# scorpion_shield_mega.net
KiCad netlist of a schematic drawn in EAGLE
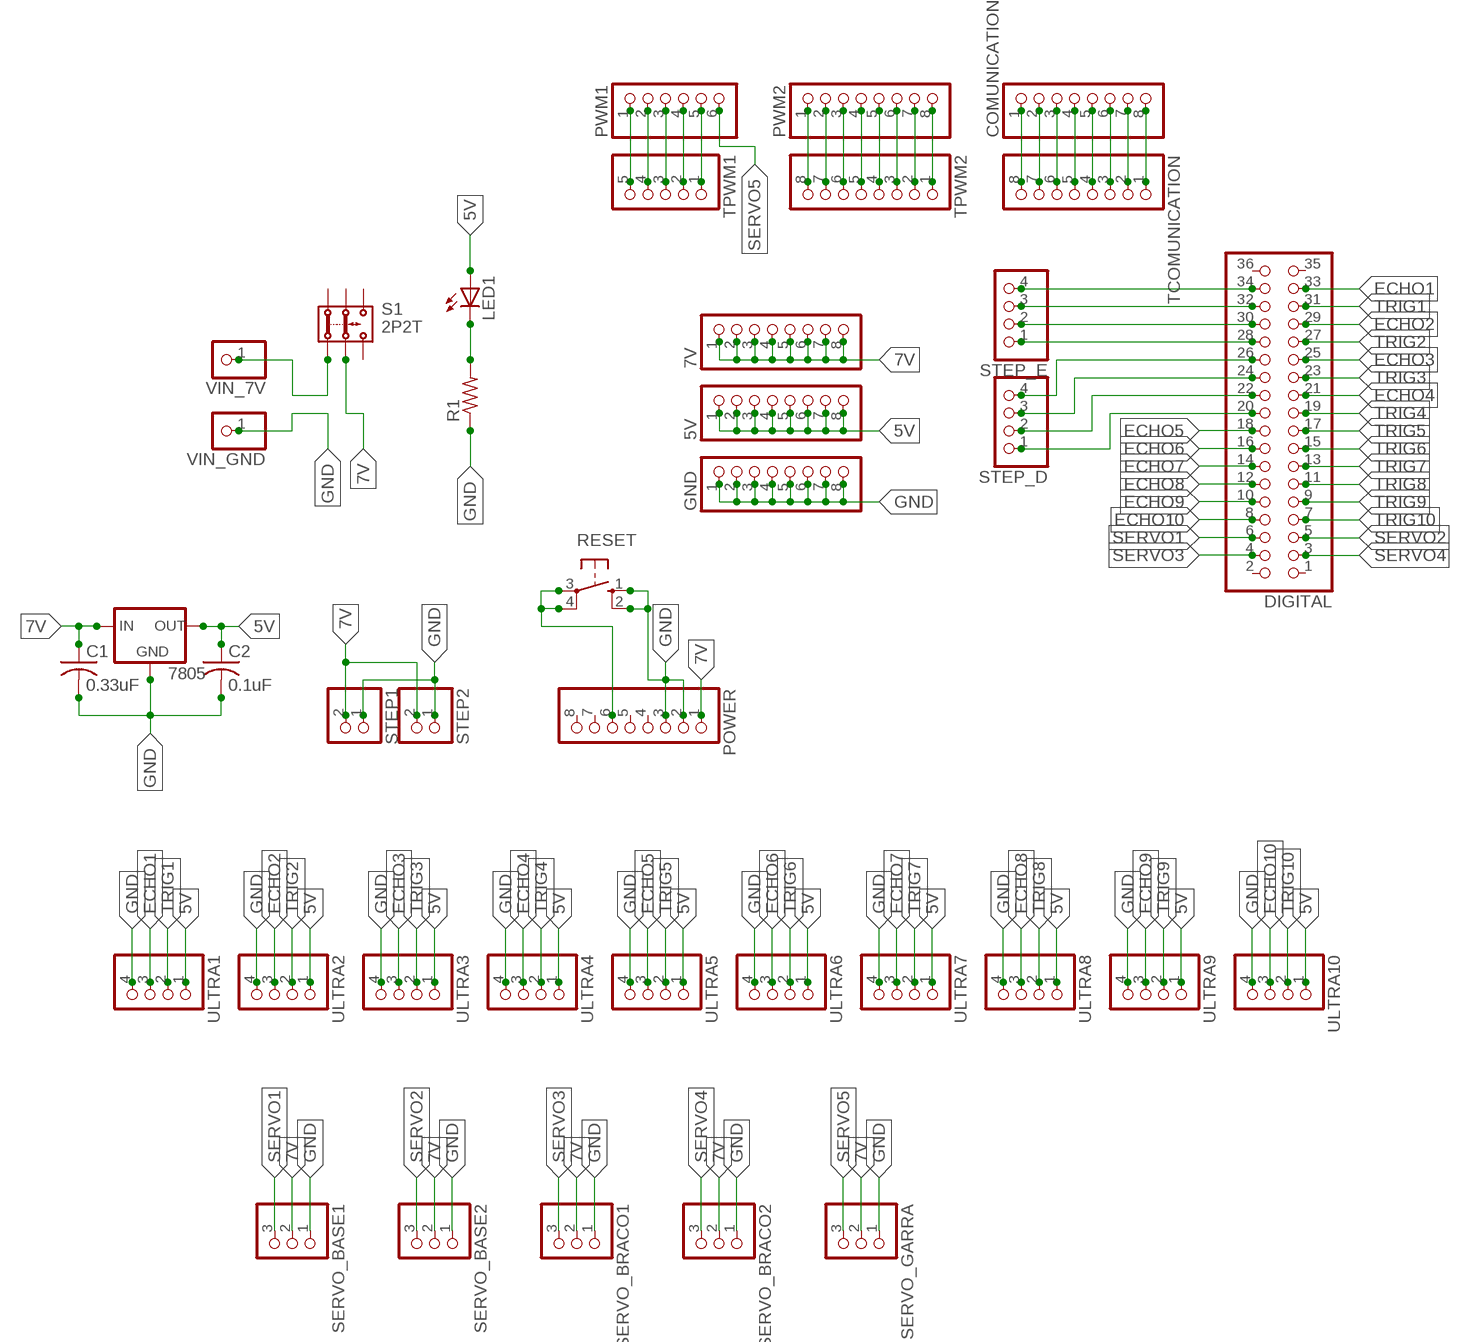
[diagram p0: schematic, sheet 1]

(export (version "E")
  (design (tool "Eeschema 10.0.6"))
  (components
    (comp (ref "5V")
      (value "PINHD-1X8")
      (footprint "eagle-import:1X08")
      (libsource (lib "eagle-import") (part "PINHD-1X8"))
    )
    (comp (ref "7V")
      (value "PINHD-1X8")
      (footprint "eagle-import:1X08")
      (libsource (lib "eagle-import") (part "PINHD-1X8"))
    )
    (comp (ref "7805")
      (value "78XXS")
      (footprint "eagle-import:78XXS")
      (libsource (lib "eagle-import") (part "78XXS"))
    )
    (comp (ref "C1")
      (value "0.33uF")
      (footprint "eagle-import:C050-025X075")
      (libsource (lib "eagle-import") (part "C-US050-025X075"))
    )
    (comp (ref "C2")
      (value "0.1uF")
      (footprint "eagle-import:C050-025X075")
      (libsource (lib "eagle-import") (part "C-US050-025X075"))
    )
    (comp (ref "COMUNICATION")
      (value "PINHD-1X8")
      (footprint "eagle-import:1X08")
      (libsource (lib "eagle-import") (part "PINHD-1X8"))
    )
    (comp (ref "DIGITAL")
      (value "PINHD-2X18")
      (footprint "eagle-import:2X18")
      (libsource (lib "eagle-import") (part "PINHD-2X18"))
    )
    (comp (ref "GND")
      (value "PINHD-1X8")
      (footprint "eagle-import:1X08")
      (libsource (lib "eagle-import") (part "PINHD-1X8"))
    )
    (comp (ref "LED1")
      (value "LED5MM")
      (footprint "eagle-import:LED5MM")
      (libsource (lib "eagle-import") (part "LED5MM"))
    )
    (comp (ref "POWER")
      (value "PINHD-1X8")
      (footprint "eagle-import:1X08")
      (libsource (lib "eagle-import") (part "PINHD-1X8"))
    )
    (comp (ref "PWM1")
      (value "PINHD-1X6")
      (footprint "eagle-import:1X06")
      (libsource (lib "eagle-import") (part "PINHD-1X6"))
    )
    (comp (ref "PWM2")
      (value "PINHD-1X8")
      (footprint "eagle-import:1X08")
      (libsource (lib "eagle-import") (part "PINHD-1X8"))
    )
    (comp (ref "R1")
      (value "R-US_0204/7")
      (footprint "eagle-import:0204_7")
      (libsource (lib "eagle-import") (part "R-US_0204/7"))
    )
    (comp (ref "RESET")
      (value "10-XX")
      (footprint "eagle-import:B3F-10XX")
      (fields (field (name "MPN") "B3F-1000"))
      (libsource (lib "eagle-import") (part "10-XX"))
    )
    (comp (ref "S1")
      (value "2P2T")
      (footprint "eagle-import:2P2T")
      (libsource (lib "eagle-import") (part "2P2T"))
    )
    (comp (ref "SERVO_BASE1")
      (value "PINHD-1X3")
      (footprint "eagle-import:1X03")
      (libsource (lib "eagle-import") (part "PINHD-1X3"))
    )
    (comp (ref "SERVO_BASE2")
      (value "PINHD-1X3")
      (footprint "eagle-import:1X03")
      (libsource (lib "eagle-import") (part "PINHD-1X3"))
    )
    (comp (ref "SERVO_BRACO1")
      (value "PINHD-1X3")
      (footprint "eagle-import:1X03")
      (libsource (lib "eagle-import") (part "PINHD-1X3"))
    )
    (comp (ref "SERVO_BRACO2")
      (value "PINHD-1X3")
      (footprint "eagle-import:1X03")
      (libsource (lib "eagle-import") (part "PINHD-1X3"))
    )
    (comp (ref "SERVO_GARRA")
      (value "PINHD-1X3")
      (footprint "eagle-import:1X03")
      (libsource (lib "eagle-import") (part "PINHD-1X3"))
    )
    (comp (ref "STEP1")
      (value "PINHD-1X2")
      (footprint "eagle-import:1X02")
      (libsource (lib "eagle-import") (part "PINHD-1X2"))
    )
    (comp (ref "STEP2")
      (value "PINHD-1X2")
      (footprint "eagle-import:1X02")
      (libsource (lib "eagle-import") (part "PINHD-1X2"))
    )
    (comp (ref "STEP_D")
      (value "PINHD-1X4")
      (footprint "eagle-import:1X04")
      (libsource (lib "eagle-import") (part "PINHD-1X4"))
    )
    (comp (ref "STEP_E")
      (value "PINHD-1X4")
      (footprint "eagle-import:1X04")
      (libsource (lib "eagle-import") (part "PINHD-1X4"))
    )
    (comp (ref "TCOMUNICATION")
      (value "PINHD-1X8")
      (footprint "eagle-import:1X08")
      (libsource (lib "eagle-import") (part "PINHD-1X8"))
    )
    (comp (ref "TPWM1")
      (value "PINHD-1X5")
      (footprint "eagle-import:1X05")
      (libsource (lib "eagle-import") (part "PINHD-1X5"))
    )
    (comp (ref "TPWM2")
      (value "PINHD-1X8")
      (footprint "eagle-import:1X08")
      (libsource (lib "eagle-import") (part "PINHD-1X8"))
    )
    (comp (ref "ULTRA1")
      (value "PINHD-1X4")
      (footprint "eagle-import:1X04")
      (libsource (lib "eagle-import") (part "PINHD-1X4"))
    )
    (comp (ref "ULTRA2")
      (value "PINHD-1X4")
      (footprint "eagle-import:1X04")
      (libsource (lib "eagle-import") (part "PINHD-1X4"))
    )
    (comp (ref "ULTRA3")
      (value "PINHD-1X4")
      (footprint "eagle-import:1X04")
      (libsource (lib "eagle-import") (part "PINHD-1X4"))
    )
    (comp (ref "ULTRA4")
      (value "PINHD-1X4")
      (footprint "eagle-import:1X04")
      (libsource (lib "eagle-import") (part "PINHD-1X4"))
    )
    (comp (ref "ULTRA5")
      (value "PINHD-1X4")
      (footprint "eagle-import:1X04")
      (libsource (lib "eagle-import") (part "PINHD-1X4"))
    )
    (comp (ref "ULTRA6")
      (value "PINHD-1X4")
      (footprint "eagle-import:1X04")
      (libsource (lib "eagle-import") (part "PINHD-1X4"))
    )
    (comp (ref "ULTRA7")
      (value "PINHD-1X4")
      (footprint "eagle-import:1X04")
      (libsource (lib "eagle-import") (part "PINHD-1X4"))
    )
    (comp (ref "ULTRA8")
      (value "PINHD-1X4")
      (footprint "eagle-import:1X04")
      (libsource (lib "eagle-import") (part "PINHD-1X4"))
    )
    (comp (ref "ULTRA9")
      (value "PINHD-1X4")
      (footprint "eagle-import:1X04")
      (libsource (lib "eagle-import") (part "PINHD-1X4"))
    )
    (comp (ref "ULTRA10")
      (value "PINHD-1X4")
      (footprint "eagle-import:1X04")
      (libsource (lib "eagle-import") (part "PINHD-1X4"))
    )
    (comp (ref "VIN_7V")
      (value "PINHD-1X1")
      (footprint "eagle-import:1X01")
      (libsource (lib "eagle-import") (part "PINHD-1X1"))
    )
    (comp (ref "VIN_GND")
      (value "PINHD-1X1")
      (footprint "eagle-import:1X01")
      (libsource (lib "eagle-import") (part "PINHD-1X1"))
    )
  )
  (nets
    (net (code "1") (name "5V") (class "Default")
      (node (ref "5V") (pin "1") (pinfunction "1_1") (pintype "passive"))
      (node (ref "5V") (pin "2") (pinfunction "2_2") (pintype "passive"))
      (node (ref "5V") (pin "3") (pinfunction "3_3") (pintype "passive"))
      (node (ref "5V") (pin "4") (pinfunction "4_4") (pintype "passive"))
      (node (ref "5V") (pin "5") (pinfunction "5_5") (pintype "passive"))
      (node (ref "5V") (pin "6") (pinfunction "6_6") (pintype "passive"))
      (node (ref "5V") (pin "7") (pinfunction "7_7") (pintype "passive"))
      (node (ref "5V") (pin "8") (pinfunction "8_8") (pintype "passive"))
      (node (ref "7805") (pin "OUT") (pinfunction "OUT_OUT") (pintype "passive"))
      (node (ref "C2") (pin "1") (pinfunction "1_1") (pintype "passive"))
      (node (ref "LED1") (pin "A") (pinfunction "A_A") (pintype "passive"))
      (node (ref "ULTRA1") (pin "1") (pinfunction "1_1") (pintype "passive"))
      (node (ref "ULTRA10") (pin "1") (pinfunction "1_1") (pintype "passive"))
      (node (ref "ULTRA2") (pin "1") (pinfunction "1_1") (pintype "passive"))
      (node (ref "ULTRA3") (pin "1") (pinfunction "1_1") (pintype "passive"))
      (node (ref "ULTRA4") (pin "1") (pinfunction "1_1") (pintype "passive"))
      (node (ref "ULTRA5") (pin "1") (pinfunction "1_1") (pintype "passive"))
      (node (ref "ULTRA6") (pin "1") (pinfunction "1_1") (pintype "passive"))
      (node (ref "ULTRA7") (pin "1") (pinfunction "1_1") (pintype "passive"))
      (node (ref "ULTRA8") (pin "1") (pinfunction "1_1") (pintype "passive"))
      (node (ref "ULTRA9") (pin "1") (pinfunction "1_1") (pintype "passive"))
    )
    (net (code "2") (name "7V") (class "Default")
      (node (ref "7805") (pin "IN") (pinfunction "IN_IN") (pintype "input"))
      (node (ref "7V") (pin "1") (pinfunction "1_1") (pintype "passive"))
      (node (ref "7V") (pin "2") (pinfunction "2_2") (pintype "passive"))
      (node (ref "7V") (pin "3") (pinfunction "3_3") (pintype "passive"))
      (node (ref "7V") (pin "4") (pinfunction "4_4") (pintype "passive"))
      (node (ref "7V") (pin "5") (pinfunction "5_5") (pintype "passive"))
      (node (ref "7V") (pin "6") (pinfunction "6_6") (pintype "passive"))
      (node (ref "7V") (pin "7") (pinfunction "7_7") (pintype "passive"))
      (node (ref "7V") (pin "8") (pinfunction "8_8") (pintype "passive"))
      (node (ref "C1") (pin "1") (pinfunction "1_1") (pintype "passive"))
      (node (ref "POWER") (pin "1") (pinfunction "1_1") (pintype "passive"))
      (node (ref "S1") (pin "2.2") (pinfunction "2.2_2.2") (pintype "passive"))
      (node (ref "SERVO_BASE1") (pin "2") (pinfunction "2_2") (pintype "passive"))
      (node (ref "SERVO_BASE2") (pin "2") (pinfunction "2_2") (pintype "passive"))
      (node (ref "SERVO_BRACO1") (pin "2") (pinfunction "2_2") (pintype "passive"))
      (node (ref "SERVO_BRACO2") (pin "2") (pinfunction "2_2") (pintype "passive"))
      (node (ref "SERVO_GARRA") (pin "2") (pinfunction "2_2") (pintype "passive"))
      (node (ref "STEP1") (pin "2") (pinfunction "2_2") (pintype "passive"))
      (node (ref "STEP2") (pin "2") (pinfunction "2_2") (pintype "passive"))
    )
    (net (code "3") (name "ECHO1") (class "Default")
      (node (ref "DIGITAL") (pin "33") (pinfunction "33_33") (pintype "passive"))
      (node (ref "ULTRA1") (pin "3") (pinfunction "3_3") (pintype "passive"))
    )
    (net (code "4") (name "ECHO2") (class "Default")
      (node (ref "DIGITAL") (pin "29") (pinfunction "29_29") (pintype "passive"))
      (node (ref "ULTRA2") (pin "3") (pinfunction "3_3") (pintype "passive"))
    )
    (net (code "5") (name "ECHO3") (class "Default")
      (node (ref "DIGITAL") (pin "25") (pinfunction "25_25") (pintype "passive"))
      (node (ref "ULTRA3") (pin "3") (pinfunction "3_3") (pintype "passive"))
    )
    (net (code "6") (name "ECHO4") (class "Default")
      (node (ref "DIGITAL") (pin "21") (pinfunction "21_21") (pintype "passive"))
      (node (ref "ULTRA4") (pin "3") (pinfunction "3_3") (pintype "passive"))
    )
    (net (code "7") (name "ECHO5") (class "Default")
      (node (ref "DIGITAL") (pin "18") (pinfunction "18_18") (pintype "passive"))
      (node (ref "ULTRA5") (pin "3") (pinfunction "3_3") (pintype "passive"))
    )
    (net (code "8") (name "ECHO6") (class "Default")
      (node (ref "DIGITAL") (pin "16") (pinfunction "16_16") (pintype "passive"))
      (node (ref "ULTRA6") (pin "3") (pinfunction "3_3") (pintype "passive"))
    )
    (net (code "9") (name "ECHO7") (class "Default")
      (node (ref "DIGITAL") (pin "14") (pinfunction "14_14") (pintype "passive"))
      (node (ref "ULTRA7") (pin "3") (pinfunction "3_3") (pintype "passive"))
    )
    (net (code "10") (name "ECHO8") (class "Default")
      (node (ref "DIGITAL") (pin "12") (pinfunction "12_12") (pintype "passive"))
      (node (ref "ULTRA8") (pin "3") (pinfunction "3_3") (pintype "passive"))
    )
    (net (code "11") (name "ECHO9") (class "Default")
      (node (ref "DIGITAL") (pin "10") (pinfunction "10_10") (pintype "passive"))
      (node (ref "ULTRA9") (pin "3") (pinfunction "3_3") (pintype "passive"))
    )
    (net (code "12") (name "ECHO10") (class "Default")
      (node (ref "DIGITAL") (pin "8") (pinfunction "8_8") (pintype "passive"))
      (node (ref "ULTRA10") (pin "3") (pinfunction "3_3") (pintype "passive"))
    )
    (net (code "13") (name "GND") (class "Default")
      (node (ref "7805") (pin "GND") (pinfunction "GND_GND") (pintype "input"))
      (node (ref "C1") (pin "2") (pinfunction "2_2") (pintype "passive"))
      (node (ref "C2") (pin "2") (pinfunction "2_2") (pintype "passive"))
      (node (ref "GND") (pin "1") (pinfunction "1_1") (pintype "passive"))
      (node (ref "GND") (pin "2") (pinfunction "2_2") (pintype "passive"))
      (node (ref "GND") (pin "3") (pinfunction "3_3") (pintype "passive"))
      (node (ref "GND") (pin "4") (pinfunction "4_4") (pintype "passive"))
      (node (ref "GND") (pin "5") (pinfunction "5_5") (pintype "passive"))
      (node (ref "GND") (pin "6") (pinfunction "6_6") (pintype "passive"))
      (node (ref "GND") (pin "7") (pinfunction "7_7") (pintype "passive"))
      (node (ref "GND") (pin "8") (pinfunction "8_8") (pintype "passive"))
      (node (ref "POWER") (pin "2") (pinfunction "2_2") (pintype "passive"))
      (node (ref "POWER") (pin "3") (pinfunction "3_3") (pintype "passive"))
      (node (ref "R1") (pin "1") (pinfunction "1_1") (pintype "passive"))
      (node (ref "RESET") (pin "1") (pinfunction "S_1") (pintype "passive"))
      (node (ref "RESET") (pin "2") (pinfunction "S1_2") (pintype "passive"))
      (node (ref "SERVO_BASE1") (pin "1") (pinfunction "1_1") (pintype "passive"))
      (node (ref "SERVO_BASE2") (pin "1") (pinfunction "1_1") (pintype "passive"))
      (node (ref "SERVO_BRACO1") (pin "1") (pinfunction "1_1") (pintype "passive"))
      (node (ref "SERVO_BRACO2") (pin "1") (pinfunction "1_1") (pintype "passive"))
      (node (ref "SERVO_GARRA") (pin "1") (pinfunction "1_1") (pintype "passive"))
      (node (ref "STEP1") (pin "1") (pinfunction "1_1") (pintype "passive"))
      (node (ref "STEP2") (pin "1") (pinfunction "1_1") (pintype "passive"))
      (node (ref "ULTRA1") (pin "4") (pinfunction "4_4") (pintype "passive"))
      (node (ref "ULTRA10") (pin "4") (pinfunction "4_4") (pintype "passive"))
      (node (ref "ULTRA2") (pin "4") (pinfunction "4_4") (pintype "passive"))
      (node (ref "ULTRA3") (pin "4") (pinfunction "4_4") (pintype "passive"))
      (node (ref "ULTRA4") (pin "4") (pinfunction "4_4") (pintype "passive"))
      (node (ref "ULTRA5") (pin "4") (pinfunction "4_4") (pintype "passive"))
      (node (ref "ULTRA6") (pin "4") (pinfunction "4_4") (pintype "passive"))
      (node (ref "ULTRA7") (pin "4") (pinfunction "4_4") (pintype "passive"))
      (node (ref "ULTRA8") (pin "4") (pinfunction "4_4") (pintype "passive"))
      (node (ref "ULTRA9") (pin "4") (pinfunction "4_4") (pintype "passive"))
      (node (ref "VIN_GND") (pin "1") (pinfunction "1_1") (pintype "passive"))
    )
    (net (code "14") (name "Net-(COMUNICATION-Pad1)") (class "Default")
      (node (ref "COMUNICATION") (pin "1") (pinfunction "1_1") (pintype "passive"))
      (node (ref "TCOMUNICATION") (pin "8") (pinfunction "8_8") (pintype "passive"))
    )
    (net (code "15") (name "Net-(COMUNICATION-Pad2)") (class "Default")
      (node (ref "COMUNICATION") (pin "2") (pinfunction "2_2") (pintype "passive"))
      (node (ref "TCOMUNICATION") (pin "7") (pinfunction "7_7") (pintype "passive"))
    )
    (net (code "16") (name "Net-(COMUNICATION-Pad3)") (class "Default")
      (node (ref "COMUNICATION") (pin "3") (pinfunction "3_3") (pintype "passive"))
      (node (ref "TCOMUNICATION") (pin "6") (pinfunction "6_6") (pintype "passive"))
    )
    (net (code "17") (name "Net-(COMUNICATION-Pad4)") (class "Default")
      (node (ref "COMUNICATION") (pin "4") (pinfunction "4_4") (pintype "passive"))
      (node (ref "TCOMUNICATION") (pin "5") (pinfunction "5_5") (pintype "passive"))
    )
    (net (code "18") (name "Net-(COMUNICATION-Pad5)") (class "Default")
      (node (ref "COMUNICATION") (pin "5") (pinfunction "5_5") (pintype "passive"))
      (node (ref "TCOMUNICATION") (pin "4") (pinfunction "4_4") (pintype "passive"))
    )
    (net (code "19") (name "Net-(COMUNICATION-Pad6)") (class "Default")
      (node (ref "COMUNICATION") (pin "6") (pinfunction "6_6") (pintype "passive"))
      (node (ref "TCOMUNICATION") (pin "3") (pinfunction "3_3") (pintype "passive"))
    )
    (net (code "20") (name "Net-(COMUNICATION-Pad7)") (class "Default")
      (node (ref "COMUNICATION") (pin "7") (pinfunction "7_7") (pintype "passive"))
      (node (ref "TCOMUNICATION") (pin "2") (pinfunction "2_2") (pintype "passive"))
    )
    (net (code "21") (name "Net-(COMUNICATION-Pad8)") (class "Default")
      (node (ref "COMUNICATION") (pin "8") (pinfunction "8_8") (pintype "passive"))
      (node (ref "TCOMUNICATION") (pin "1") (pinfunction "1_1") (pintype "passive"))
    )
    (net (code "22") (name "Net-(DIGITAL-Pad20)") (class "Default")
      (node (ref "DIGITAL") (pin "20") (pinfunction "20_20") (pintype "passive"))
      (node (ref "STEP_D") (pin "1") (pinfunction "1_1") (pintype "passive"))
    )
    (net (code "23") (name "Net-(DIGITAL-Pad22)") (class "Default")
      (node (ref "DIGITAL") (pin "22") (pinfunction "22_22") (pintype "passive"))
      (node (ref "STEP_D") (pin "2") (pinfunction "2_2") (pintype "passive"))
    )
    (net (code "24") (name "Net-(DIGITAL-Pad24)") (class "Default")
      (node (ref "DIGITAL") (pin "24") (pinfunction "24_24") (pintype "passive"))
      (node (ref "STEP_D") (pin "3") (pinfunction "3_3") (pintype "passive"))
    )
    (net (code "25") (name "Net-(DIGITAL-Pad26)") (class "Default")
      (node (ref "DIGITAL") (pin "26") (pinfunction "26_26") (pintype "passive"))
      (node (ref "STEP_D") (pin "4") (pinfunction "4_4") (pintype "passive"))
    )
    (net (code "26") (name "Net-(DIGITAL-Pad28)") (class "Default")
      (node (ref "DIGITAL") (pin "28") (pinfunction "28_28") (pintype "passive"))
      (node (ref "STEP_E") (pin "1") (pinfunction "1_1") (pintype "passive"))
    )
    (net (code "27") (name "Net-(DIGITAL-Pad30)") (class "Default")
      (node (ref "DIGITAL") (pin "30") (pinfunction "30_30") (pintype "passive"))
      (node (ref "STEP_E") (pin "2") (pinfunction "2_2") (pintype "passive"))
    )
    (net (code "28") (name "Net-(DIGITAL-Pad32)") (class "Default")
      (node (ref "DIGITAL") (pin "32") (pinfunction "32_32") (pintype "passive"))
      (node (ref "STEP_E") (pin "3") (pinfunction "3_3") (pintype "passive"))
    )
    (net (code "29") (name "Net-(DIGITAL-Pad34)") (class "Default")
      (node (ref "DIGITAL") (pin "34") (pinfunction "34_34") (pintype "passive"))
      (node (ref "STEP_E") (pin "4") (pinfunction "4_4") (pintype "passive"))
    )
    (net (code "30") (name "Net-(LED1-C)") (class "Default")
      (node (ref "LED1") (pin "K") (pinfunction "C_K") (pintype "passive"))
      (node (ref "R1") (pin "2") (pinfunction "2_2") (pintype "passive"))
    )
    (net (code "31") (name "Net-(PWM1-Pad1)") (class "Default")
      (node (ref "PWM1") (pin "1") (pinfunction "1_1") (pintype "passive"))
      (node (ref "TPWM1") (pin "5") (pinfunction "5_5") (pintype "passive"))
    )
    (net (code "32") (name "Net-(PWM1-Pad2)") (class "Default")
      (node (ref "PWM1") (pin "2") (pinfunction "2_2") (pintype "passive"))
      (node (ref "TPWM1") (pin "4") (pinfunction "4_4") (pintype "passive"))
    )
    (net (code "33") (name "Net-(PWM1-Pad3)") (class "Default")
      (node (ref "PWM1") (pin "3") (pinfunction "3_3") (pintype "passive"))
      (node (ref "TPWM1") (pin "3") (pinfunction "3_3") (pintype "passive"))
    )
    (net (code "34") (name "Net-(PWM1-Pad4)") (class "Default")
      (node (ref "PWM1") (pin "4") (pinfunction "4_4") (pintype "passive"))
      (node (ref "TPWM1") (pin "2") (pinfunction "2_2") (pintype "passive"))
    )
    (net (code "35") (name "Net-(PWM1-Pad5)") (class "Default")
      (node (ref "PWM1") (pin "5") (pinfunction "5_5") (pintype "passive"))
      (node (ref "TPWM1") (pin "1") (pinfunction "1_1") (pintype "passive"))
    )
    (net (code "36") (name "Net-(PWM2-Pad1)") (class "Default")
      (node (ref "PWM2") (pin "1") (pinfunction "1_1") (pintype "passive"))
      (node (ref "TPWM2") (pin "8") (pinfunction "8_8") (pintype "passive"))
    )
    (net (code "37") (name "Net-(PWM2-Pad2)") (class "Default")
      (node (ref "PWM2") (pin "2") (pinfunction "2_2") (pintype "passive"))
      (node (ref "TPWM2") (pin "7") (pinfunction "7_7") (pintype "passive"))
    )
    (net (code "38") (name "Net-(PWM2-Pad3)") (class "Default")
      (node (ref "PWM2") (pin "3") (pinfunction "3_3") (pintype "passive"))
      (node (ref "TPWM2") (pin "6") (pinfunction "6_6") (pintype "passive"))
    )
    (net (code "39") (name "Net-(PWM2-Pad4)") (class "Default")
      (node (ref "PWM2") (pin "4") (pinfunction "4_4") (pintype "passive"))
      (node (ref "TPWM2") (pin "5") (pinfunction "5_5") (pintype "passive"))
    )
    (net (code "40") (name "Net-(PWM2-Pad5)") (class "Default")
      (node (ref "PWM2") (pin "5") (pinfunction "5_5") (pintype "passive"))
      (node (ref "TPWM2") (pin "4") (pinfunction "4_4") (pintype "passive"))
    )
    (net (code "41") (name "Net-(PWM2-Pad6)") (class "Default")
      (node (ref "PWM2") (pin "6") (pinfunction "6_6") (pintype "passive"))
      (node (ref "TPWM2") (pin "3") (pinfunction "3_3") (pintype "passive"))
    )
    (net (code "42") (name "Net-(PWM2-Pad7)") (class "Default")
      (node (ref "PWM2") (pin "7") (pinfunction "7_7") (pintype "passive"))
      (node (ref "TPWM2") (pin "2") (pinfunction "2_2") (pintype "passive"))
    )
    (net (code "43") (name "Net-(PWM2-Pad8)") (class "Default")
      (node (ref "PWM2") (pin "8") (pinfunction "8_8") (pintype "passive"))
      (node (ref "TPWM2") (pin "1") (pinfunction "1_1") (pintype "passive"))
    )
    (net (code "44") (name "Net-(RESET-P)") (class "Default")
      (node (ref "POWER") (pin "6") (pinfunction "6_6") (pintype "passive"))
      (node (ref "RESET") (pin "3") (pinfunction "P_3") (pintype "passive"))
      (node (ref "RESET") (pin "4") (pinfunction "P1_4") (pintype "passive"))
    )
    (net (code "45") (name "Net-(S1-Pad1.2)") (class "Default")
      (node (ref "S1") (pin "1.2") (pinfunction "1.2_1.2") (pintype "passive"))
      (node (ref "VIN_7V") (pin "1") (pinfunction "1_1") (pintype "passive"))
    )
    (net (code "46") (name "SERVO1") (class "Default")
      (node (ref "DIGITAL") (pin "6") (pinfunction "6_6") (pintype "passive"))
      (node (ref "SERVO_BASE1") (pin "3") (pinfunction "3_3") (pintype "passive"))
    )
    (net (code "47") (name "SERVO2") (class "Default")
      (node (ref "DIGITAL") (pin "5") (pinfunction "5_5") (pintype "passive"))
      (node (ref "SERVO_BASE2") (pin "3") (pinfunction "3_3") (pintype "passive"))
    )
    (net (code "48") (name "SERVO3") (class "Default")
      (node (ref "DIGITAL") (pin "4") (pinfunction "4_4") (pintype "passive"))
      (node (ref "SERVO_BRACO1") (pin "3") (pinfunction "3_3") (pintype "passive"))
    )
    (net (code "49") (name "SERVO4") (class "Default")
      (node (ref "DIGITAL") (pin "3") (pinfunction "3_3") (pintype "passive"))
      (node (ref "SERVO_BRACO2") (pin "3") (pinfunction "3_3") (pintype "passive"))
    )
    (net (code "50") (name "SERVO5") (class "Default")
      (node (ref "PWM1") (pin "6") (pinfunction "6_6") (pintype "passive"))
      (node (ref "SERVO_GARRA") (pin "3") (pinfunction "3_3") (pintype "passive"))
    )
    (net (code "51") (name "TRIG1") (class "Default")
      (node (ref "DIGITAL") (pin "31") (pinfunction "31_31") (pintype "passive"))
      (node (ref "ULTRA1") (pin "2") (pinfunction "2_2") (pintype "passive"))
    )
    (net (code "52") (name "TRIG2") (class "Default")
      (node (ref "DIGITAL") (pin "27") (pinfunction "27_27") (pintype "passive"))
      (node (ref "ULTRA2") (pin "2") (pinfunction "2_2") (pintype "passive"))
    )
    (net (code "53") (name "TRIG3") (class "Default")
      (node (ref "DIGITAL") (pin "23") (pinfunction "23_23") (pintype "passive"))
      (node (ref "ULTRA3") (pin "2") (pinfunction "2_2") (pintype "passive"))
    )
    (net (code "54") (name "TRIG4") (class "Default")
      (node (ref "DIGITAL") (pin "19") (pinfunction "19_19") (pintype "passive"))
      (node (ref "ULTRA4") (pin "2") (pinfunction "2_2") (pintype "passive"))
    )
    (net (code "55") (name "TRIG5") (class "Default")
      (node (ref "DIGITAL") (pin "17") (pinfunction "17_17") (pintype "passive"))
      (node (ref "ULTRA5") (pin "2") (pinfunction "2_2") (pintype "passive"))
    )
    (net (code "56") (name "TRIG6") (class "Default")
      (node (ref "DIGITAL") (pin "15") (pinfunction "15_15") (pintype "passive"))
      (node (ref "ULTRA6") (pin "2") (pinfunction "2_2") (pintype "passive"))
    )
    (net (code "57") (name "TRIG7") (class "Default")
      (node (ref "DIGITAL") (pin "13") (pinfunction "13_13") (pintype "passive"))
      (node (ref "ULTRA7") (pin "2") (pinfunction "2_2") (pintype "passive"))
    )
    (net (code "58") (name "TRIG8") (class "Default")
      (node (ref "DIGITAL") (pin "11") (pinfunction "11_11") (pintype "passive"))
      (node (ref "ULTRA8") (pin "2") (pinfunction "2_2") (pintype "passive"))
    )
    (net (code "59") (name "TRIG9") (class "Default")
      (node (ref "DIGITAL") (pin "9") (pinfunction "9_9") (pintype "passive"))
      (node (ref "ULTRA9") (pin "2") (pinfunction "2_2") (pintype "passive"))
    )
    (net (code "60") (name "TRIG10") (class "Default")
      (node (ref "DIGITAL") (pin "7") (pinfunction "7_7") (pintype "passive"))
      (node (ref "ULTRA10") (pin "2") (pinfunction "2_2") (pintype "passive"))
    )
    (net (code "61") (name "unconnected-(DIGITAL-Pad1)") (class "Default")
      (node (ref "DIGITAL") (pin "1") (pinfunction "1_1") (pintype "passive"))
    )
    (net (code "62") (name "unconnected-(DIGITAL-Pad2)") (class "Default")
      (node (ref "DIGITAL") (pin "2") (pinfunction "2_2") (pintype "passive"))
    )
    (net (code "63") (name "unconnected-(DIGITAL-Pad35)") (class "Default")
      (node (ref "DIGITAL") (pin "35") (pinfunction "35_35") (pintype "passive"))
    )
    (net (code "64") (name "unconnected-(DIGITAL-Pad36)") (class "Default")
      (node (ref "DIGITAL") (pin "36") (pinfunction "36_36") (pintype "passive"))
    )
    (net (code "65") (name "unconnected-(POWER-Pad4)") (class "Default")
      (node (ref "POWER") (pin "4") (pinfunction "4_4") (pintype "passive"))
    )
    (net (code "66") (name "unconnected-(POWER-Pad5)") (class "Default")
      (node (ref "POWER") (pin "5") (pinfunction "5_5") (pintype "passive"))
    )
    (net (code "67") (name "unconnected-(POWER-Pad7)") (class "Default")
      (node (ref "POWER") (pin "7") (pinfunction "7_7") (pintype "passive"))
    )
    (net (code "68") (name "unconnected-(POWER-Pad8)") (class "Default")
      (node (ref "POWER") (pin "8") (pinfunction "8_8") (pintype "passive"))
    )
    (net (code "69") (name "unconnected-(S1-Pad1.1)") (class "Default")
      (node (ref "S1") (pin "1.1") (pinfunction "1.1_1.1") (pintype "passive"))
    )
    (net (code "70") (name "unconnected-(S1-Pad2.1)") (class "Default")
      (node (ref "S1") (pin "2.1") (pinfunction "2.1_2.1") (pintype "passive"))
    )
    (net (code "71") (name "unconnected-(S1-Pad3.1)") (class "Default")
      (node (ref "S1") (pin "3.1") (pinfunction "3.1_3.1") (pintype "passive"))
    )
    (net (code "72") (name "unconnected-(S1-Pad3.2)") (class "Default")
      (node (ref "S1") (pin "3.2") (pinfunction "3.2_3.2") (pintype "passive"))
    )
  )
)
